# Sch.net
KiCad netlist of a schematic drawn in Altium Designer
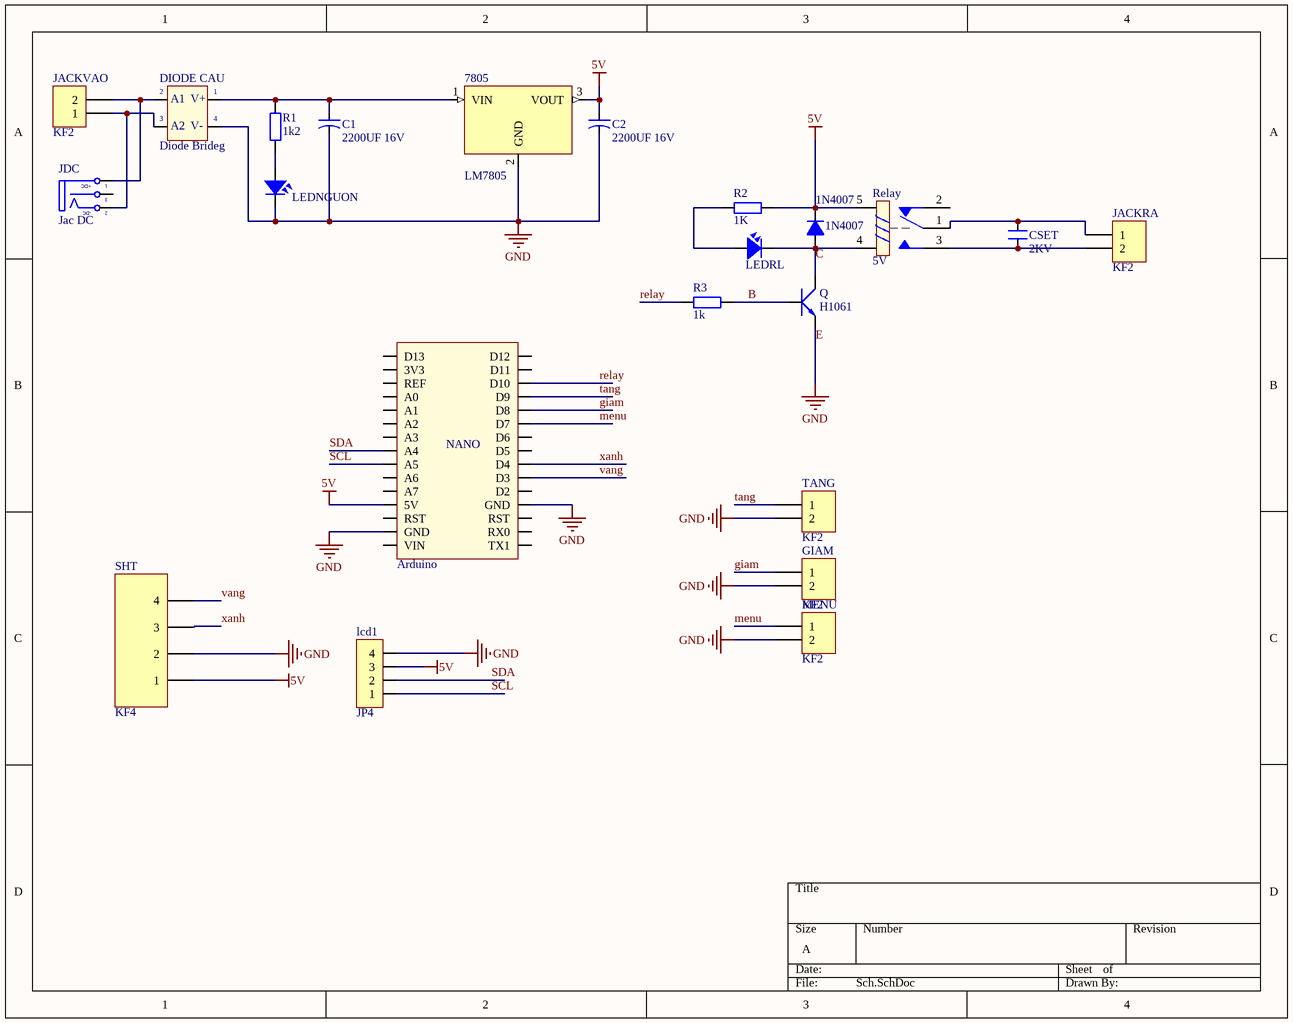
[diagram p0: Sch.SchDoc]

(export (version "E")
  (design (tool "Eeschema 10.0.6"))
  (components
    (comp (ref "1N4007")
      (value "1N4007")
      (footprint "D1A")
      (description "Diode 1A")
      (libsource (lib "Cty1") (part "D1A"))
    )
    (comp (ref "7805")
      (value "LM7805")
      (footprint "QTO-220H3")
      (description "TO-220")
      (libsource (lib "Cty1") (part "LM7805"))
    )
    (comp (ref "Arduino")
      (value "Arduino Nano")
      (footprint "Arduino Nano")
      (description "Arduino NANO")
      (libsource (lib "LIBRARY") (part "Arduino Nano"))
    )
    (comp (ref "C1")
      (value "2200UF 16V")
      (footprint "CA-ALU-8")
      (description "Capacitor (Semiconductor SIM Model)")
      (fields (field (name "PUBLISHER") "Altium Limited"))
      (libsource (lib "LIBRARY") (part "CN-ALU-DIP"))
    )
    (comp (ref "C2")
      (value "2200UF 16V")
      (footprint "CA-ALU-8")
      (description "Capacitor (Semiconductor SIM Model)")
      (fields (field (name "PUBLISHER") "Altium Limited"))
      (libsource (lib "LIBRARY") (part "CN-ALU-DIP"))
    )
    (comp (ref "CSET") (value "2KV") (footprint "CN2.5") (libsource (lib "LIBRARY") (part "CN")))
    (comp (ref "DIODE CAU")
      (value "Diode Brideg")
      (footprint "DIO-Bri 5A")
      (description "Convert AC to DC voltage, 4 pin")
      (libsource (lib "LIBRARY") (part "DIODE BRIGDE"))
    )
    (comp (ref "GIAM")
      (value "KF2")
      (footprint "KF2-3.5")
      (fields
        (field (name "MANUFACTURER") "Würth Elektronik eiSos GmbH")
        (field (name "PARTNO") "691103110002")
        (field (name "CREATED BY") "Karrer Zheng")
      )
      (libsource (lib "LIBRARY") (part "KF2"))
    )
    (comp (ref "JACKRA")
      (value "KF2")
      (footprint "KF2-5.08")
      (fields
        (field (name "MANUFACTURER") "Würth Elektronik eiSos GmbH")
        (field (name "PARTNO") "691103110002")
        (field (name "CREATED BY") "Karrer Zheng")
      )
      (libsource (lib "LIBRARY") (part "KF2"))
    )
    (comp (ref "JACKVAO")
      (value "KF2")
      (footprint "KF2-3.5")
      (fields
        (field (name "MANUFACTURER") "Würth Elektronik eiSos GmbH")
        (field (name "PARTNO") "691103110002")
        (field (name "CREATED BY") "Karrer Zheng")
      )
      (libsource (lib "") (part "KF2_1"))
    )
    (comp (ref "JDC")
      (value "Jac DC")
      (footprint "DC0")
      (description "Jac DC input")
      (libsource (lib "LIBRARY") (part "DCIN"))
    )
    (comp (ref "lcd1")
      (value "JP4")
      (footprint "JP4-C1T")
      (description "WR-PHD 2.54 mm Angled Socket Header")
      (fields
        (field (name "MANUFACTURER") "Würth Elektronik eiSos GmbH")
        (field (name "PARTNO") "613004143121")
        (field (name "CREATED BY") "Karrer Zheng")
      )
      (libsource (lib "LIBRARY") (part "JP4"))
    )
    (comp (ref "LEDNGUON")
      (value "LED")
      (footprint "LED-5-BLUE")
      (description "LED Single colour Green and Red")
      (libsource (lib "LIBRARY") (part "LED"))
    )
    (comp (ref "LEDRL")
      (value "LED")
      (footprint "LED-5-RED")
      (description "LED Single colour Green and Red")
      (libsource (lib "LIBRARY") (part "LED"))
    )
    (comp (ref "MENU")
      (value "KF2")
      (footprint "KF2-3.5")
      (fields
        (field (name "MANUFACTURER") "Würth Elektronik eiSos GmbH")
        (field (name "PARTNO") "691103110002")
        (field (name "CREATED BY") "Karrer Zheng")
      )
      (libsource (lib "LIBRARY") (part "KF2"))
    )
    (comp (ref "Q")
      (value "H1061")
      (footprint "QTO-220")
      (description "P 1W, BCE")
      (libsource (lib "syhaunguyen") (part "NPN_BCE"))
    )
    (comp (ref "R1")
      (value "1k2")
      (footprint "R1/4W")
      (description "Resistor 1/4W")
      (libsource (lib "Cty1") (part "R1/4W"))
    )
    (comp (ref "R2")
      (value "1K")
      (footprint "R1/4W")
      (description "Resistor 1/4W")
      (libsource (lib "Cty1") (part "R1/4W"))
    )
    (comp (ref "R3")
      (value "1k")
      (footprint "R1/4W")
      (description "Resistor 1/4W")
      (libsource (lib "Cty1") (part "R1/4W"))
    )
    (comp (ref "Relay")
      (value "5V")
      (footprint "RELAY 5")
      (description "Relay SPDT,10A - 12VDC 5 Pin")
      (libsource (lib "LIBRARY") (part "Relay 5"))
    )
    (comp (ref "SHT")
      (value "KF4")
      (footprint "KF4-5.08")
      (fields
        (field (name "MANUFACTURER") "Würth Elektronik eiSos GmbH")
        (field (name "PARTNO") "691133710004")
        (field (name "CREATED BY") "Baojun Chen")
      )
      (libsource (lib "LIBRARY") (part "KF4"))
    )
    (comp (ref "TANG")
      (value "KF2")
      (footprint "KF2-3.5")
      (fields
        (field (name "MANUFACTURER") "Würth Elektronik eiSos GmbH")
        (field (name "PARTNO") "691103110002")
        (field (name "CREATED BY") "Karrer Zheng")
      )
      (libsource (lib "LIBRARY") (part "KF2"))
    )
  )
  (nets
    (net (code "1") (name "/B") (class "Default")
      (node (ref "Q") (pin "1") (pinfunction "B_1") (pintype "passive"))
      (node (ref "R3") (pin "2") (pinfunction "2_2") (pintype "passive"))
    )
    (net (code "2") (name "/C") (class "Default")
      (node (ref "1N4007") (pin "1") (pinfunction "A_1") (pintype "passive"))
      (node (ref "LEDRL") (pin "2") (pinfunction "2_2") (pintype "passive"))
      (node (ref "Q") (pin "2") (pinfunction "C_2") (pintype "passive"))
      (node (ref "Relay") (pin "4") (pinfunction "4_4") (pintype "passive"))
    )
    (net (code "3") (name "/SCL") (class "Default")
      (node (ref "Arduino") (pin "A5") (pinfunction "A5_A5") (pintype "passive"))
      (node (ref "lcd1") (pin "1") (pinfunction "1_1") (pintype "passive"))
    )
    (net (code "4") (name "/SDA") (class "Default")
      (node (ref "Arduino") (pin "A4") (pinfunction "A4_A4") (pintype "passive"))
      (node (ref "lcd1") (pin "2") (pinfunction "2_2") (pintype "passive"))
    )
    (net (code "5") (name "/giam") (class "Default")
      (node (ref "Arduino") (pin "D8") (pinfunction "D8_D8") (pintype "passive"))
      (node (ref "GIAM") (pin "1") (pinfunction "1_1") (pintype "passive"))
    )
    (net (code "6") (name "/menu") (class "Default")
      (node (ref "Arduino") (pin "D7") (pinfunction "D7_D7") (pintype "passive"))
      (node (ref "MENU") (pin "1") (pinfunction "1_1") (pintype "passive"))
    )
    (net (code "7") (name "/relay") (class "Default")
      (node (ref "Arduino") (pin "D10") (pinfunction "D10_D10") (pintype "passive"))
      (node (ref "R3") (pin "1") (pinfunction "1_1") (pintype "passive"))
    )
    (net (code "8") (name "/tang") (class "Default")
      (node (ref "Arduino") (pin "D9") (pinfunction "D9_D9") (pintype "passive"))
      (node (ref "TANG") (pin "1") (pinfunction "1_1") (pintype "passive"))
    )
    (net (code "9") (name "/vang") (class "Default")
      (node (ref "Arduino") (pin "D3") (pinfunction "D3_D3") (pintype "passive"))
      (node (ref "SHT") (pin "4") (pinfunction "4_4") (pintype "passive"))
    )
    (net (code "10") (name "/xanh") (class "Default")
      (node (ref "Arduino") (pin "D4") (pinfunction "D4_D4") (pintype "passive"))
      (node (ref "SHT") (pin "3") (pinfunction "3_3") (pintype "passive"))
    )
    (net (code "11") (name "5V") (class "Default")
      (node (ref "1N4007") (pin "2") (pinfunction "K_2") (pintype "passive"))
      (node (ref "7805") (pin "3") (pinfunction "VOUT_3") (pintype "output"))
      (node (ref "Arduino") (pin "5V") (pinfunction "5V_5V") (pintype "passive"))
      (node (ref "C2") (pin "1") (pinfunction "1_1") (pintype "passive"))
      (node (ref "R2") (pin "2") (pinfunction "2_2") (pintype "passive"))
      (node (ref "Relay") (pin "5") (pinfunction "5_5") (pintype "passive"))
      (node (ref "SHT") (pin "1") (pinfunction "1_1") (pintype "passive"))
      (node (ref "lcd1") (pin "3") (pinfunction "3_3") (pintype "passive"))
    )
    (net (code "12") (name "GND") (class "Default")
      (node (ref "7805") (pin "2") (pinfunction "GND_2") (pintype "power_in"))
      (node (ref "Arduino") (pin "GND") (pinfunction "GND_GND") (pintype "passive"))
      (node (ref "C1") (pin "2") (pinfunction "2_2") (pintype "passive"))
      (node (ref "C2") (pin "2") (pinfunction "2_2") (pintype "passive"))
      (node (ref "DIODE CAU") (pin "4") (pinfunction "-V_OUT_4") (pintype "passive"))
      (node (ref "GIAM") (pin "2") (pinfunction "2_2") (pintype "passive"))
      (node (ref "LEDNGUON") (pin "2") (pinfunction "2_2") (pintype "passive"))
      (node (ref "MENU") (pin "2") (pinfunction "2_2") (pintype "passive"))
      (node (ref "Q") (pin "3") (pinfunction "E_3") (pintype "passive"))
      (node (ref "SHT") (pin "2") (pinfunction "2_2") (pintype "passive"))
      (node (ref "TANG") (pin "2") (pinfunction "2_2") (pintype "passive"))
      (node (ref "lcd1") (pin "4") (pinfunction "4_4") (pintype "passive"))
    )
    (net (code "13") (name "Net-(7805-VIN)") (class "Default")
      (node (ref "7805") (pin "1") (pinfunction "VIN_1") (pintype "input"))
      (node (ref "C1") (pin "1") (pinfunction "1_1") (pintype "passive"))
      (node (ref "DIODE CAU") (pin "1") (pinfunction "+V_OUT_1") (pintype "passive"))
      (node (ref "R1") (pin "2") (pinfunction "2_2") (pintype "passive"))
    )
    (net (code "14") (name "Net-(CSET-Pad1)") (class "Default")
      (node (ref "CSET") (pin "1") (pinfunction "1_1") (pintype "passive"))
      (node (ref "JACKRA") (pin "2") (pinfunction "2_2") (pintype "passive"))
      (node (ref "Relay") (pin "3") (pinfunction "3_3") (pintype "passive"))
    )
    (net (code "15") (name "Net-(CSET-Pad2)") (class "Default")
      (node (ref "CSET") (pin "2") (pinfunction "2_2") (pintype "passive"))
      (node (ref "JACKRA") (pin "1") (pinfunction "1_1") (pintype "passive"))
      (node (ref "Relay") (pin "1") (pinfunction "1_1") (pintype "passive"))
    )
    (net (code "16") (name "Net-(DIODE CAU-AC1)") (class "Default")
      (node (ref "DIODE CAU") (pin "2") (pinfunction "AC1_2") (pintype "passive"))
      (node (ref "JACKVAO") (pin "2") (pinfunction "2_2") (pintype "passive"))
      (node (ref "JDC") (pin "1") (pinfunction "T_1") (pintype "passive"))
    )
    (net (code "17") (name "Net-(DIODE CAU-AC2)") (class "Default")
      (node (ref "DIODE CAU") (pin "3") (pinfunction "AC2_3") (pintype "passive"))
      (node (ref "JACKVAO") (pin "1") (pinfunction "1_1") (pintype "passive"))
      (node (ref "JDC") (pin "2") (pinfunction "TN_2") (pintype "passive"))
    )
    (net (code "18") (name "Net-(LEDNGUON-Pad1)") (class "Default")
      (node (ref "LEDNGUON") (pin "1") (pinfunction "1_1") (pintype "passive"))
      (node (ref "R1") (pin "1") (pinfunction "1_1") (pintype "passive"))
    )
    (net (code "19") (name "Net-(LEDRL-Pad1)") (class "Default")
      (node (ref "LEDRL") (pin "1") (pinfunction "1_1") (pintype "passive"))
      (node (ref "R2") (pin "1") (pinfunction "1_1") (pintype "passive"))
    )
    (net (code "20") (name "unconnected-(Arduino-Pad3V3)") (class "Default")
      (node (ref "Arduino") (pin "3V3") (pinfunction "3V3_3V3") (pintype "passive"))
    )
    (net (code "21") (name "unconnected-(Arduino-PadA0)") (class "Default")
      (node (ref "Arduino") (pin "A0") (pinfunction "A0_A0") (pintype "passive"))
    )
    (net (code "22") (name "unconnected-(Arduino-PadA1)") (class "Default")
      (node (ref "Arduino") (pin "A1") (pinfunction "A1_A1") (pintype "passive"))
    )
    (net (code "23") (name "unconnected-(Arduino-PadA2)") (class "Default")
      (node (ref "Arduino") (pin "A2") (pinfunction "A2_A2") (pintype "passive"))
    )
    (net (code "24") (name "unconnected-(Arduino-PadA3)") (class "Default")
      (node (ref "Arduino") (pin "A3") (pinfunction "A3_A3") (pintype "passive"))
    )
    (net (code "25") (name "unconnected-(Arduino-PadA6)") (class "Default")
      (node (ref "Arduino") (pin "A6") (pinfunction "A6_A6") (pintype "passive"))
    )
    (net (code "26") (name "unconnected-(Arduino-PadA7)") (class "Default")
      (node (ref "Arduino") (pin "A7") (pinfunction "A7_A7") (pintype "passive"))
    )
    (net (code "27") (name "unconnected-(Arduino-PadD2)") (class "Default")
      (node (ref "Arduino") (pin "D2") (pinfunction "D2_D2") (pintype "passive"))
    )
    (net (code "28") (name "unconnected-(Arduino-PadD5)") (class "Default")
      (node (ref "Arduino") (pin "D5") (pinfunction "D5_D5") (pintype "passive"))
    )
    (net (code "29") (name "unconnected-(Arduino-PadD6)") (class "Default")
      (node (ref "Arduino") (pin "D6") (pinfunction "D6_D6") (pintype "passive"))
    )
    (net (code "30") (name "unconnected-(Arduino-PadD11)") (class "Default")
      (node (ref "Arduino") (pin "D11") (pinfunction "D11_D11") (pintype "passive"))
    )
    (net (code "31") (name "unconnected-(Arduino-PadD12)") (class "Default")
      (node (ref "Arduino") (pin "D12") (pinfunction "D12_D12") (pintype "passive"))
    )
    (net (code "32") (name "unconnected-(Arduino-PadD13)") (class "Default")
      (node (ref "Arduino") (pin "D13") (pinfunction "D13_D13") (pintype "passive"))
    )
    (net (code "33") (name "unconnected-(Arduino-PadREF)") (class "Default")
      (node (ref "Arduino") (pin "REF") (pinfunction "REF_REF") (pintype "passive"))
    )
    (net (code "34") (name "unconnected-(Arduino-PadRST)") (class "Default")
      (node (ref "Arduino") (pin "RST") (pinfunction "RST_RST") (pintype "passive"))
    )
    (net (code "35") (name "unconnected-(Arduino-PadRST)_1") (class "Default")
      (node (ref "Arduino") (pin "RST") (pinfunction "RST_RST") (pintype "passive"))
    )
    (net (code "36") (name "unconnected-(Arduino-PadRX0)") (class "Default")
      (node (ref "Arduino") (pin "RX0") (pinfunction "RX0_RX0") (pintype "passive"))
    )
    (net (code "37") (name "unconnected-(Arduino-PadTX1)") (class "Default")
      (node (ref "Arduino") (pin "TX1") (pinfunction "TX1_TX1") (pintype "passive"))
    )
    (net (code "38") (name "unconnected-(Arduino-PadVIN)") (class "Default")
      (node (ref "Arduino") (pin "VIN") (pinfunction "VIN_VIN") (pintype "passive"))
    )
    (net (code "39") (name "unconnected-(JDC-S-Pad3)") (class "Default")
      (node (ref "JDC") (pin "3") (pinfunction "S_3") (pintype "power_in"))
    )
    (net (code "40") (name "unconnected-(Relay-Pad2)") (class "Default")
      (node (ref "Relay") (pin "2") (pinfunction "2_2") (pintype "passive"))
    )
  )
)
